# PGTN_daisy1_controls.net
KiCad netlist of a schematic drawn in EAGLE
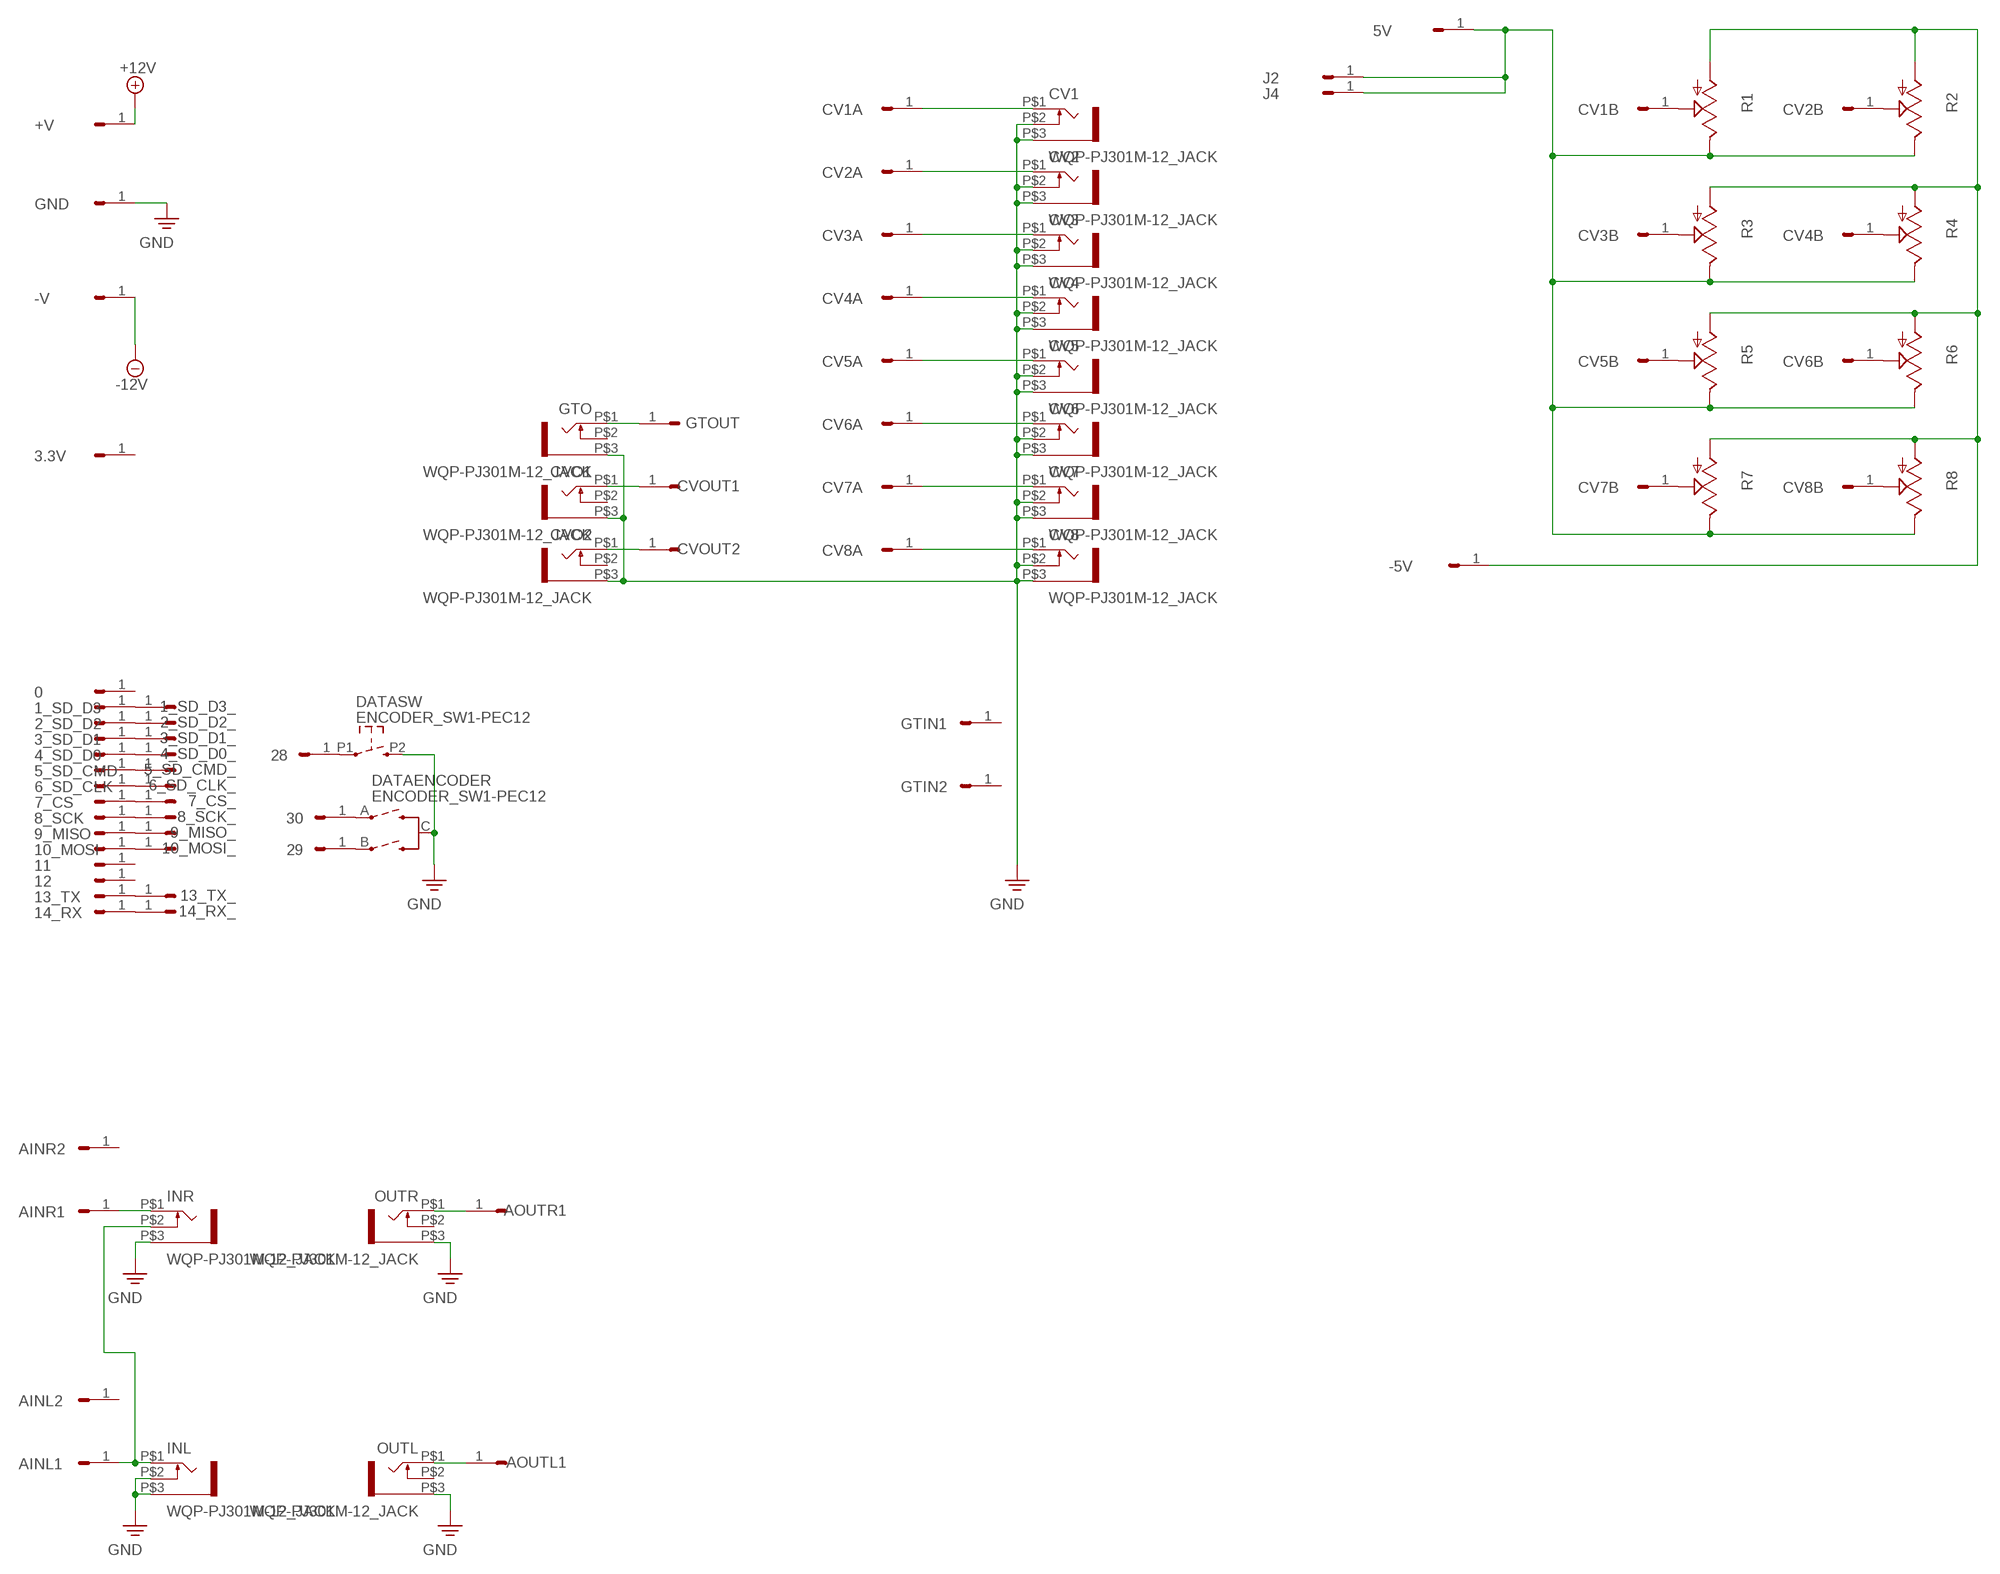
[diagram p0: schematic, sheet 1]

(export (version "E")
  (design (tool "Eeschema 10.0.6"))
  (components
    (comp (ref "+V")
      (value "HEADER/MALE/01")
      (footprint "eagle-import:HEADER_MALE_01")
      (fields (field (name "SPICEPREFIX") "X"))
      (libsource (lib "eagle-import") (part "HEADER/MALE/01"))
    )
    (comp (ref "-5V")
      (value "HEADER/MALE/01")
      (footprint "eagle-import:HEADER_MALE_01")
      (fields (field (name "SPICEPREFIX") "X"))
      (libsource (lib "eagle-import") (part "HEADER/MALE/01"))
    )
    (comp (ref "-V")
      (value "HEADER/MALE/01")
      (footprint "eagle-import:HEADER_MALE_01")
      (fields (field (name "SPICEPREFIX") "X"))
      (libsource (lib "eagle-import") (part "HEADER/MALE/01"))
    )
    (comp (ref "0")
      (value "HEADER/MALE/01")
      (footprint "eagle-import:HEADER_MALE_01")
      (fields (field (name "SPICEPREFIX") "X"))
      (libsource (lib "eagle-import") (part "HEADER/MALE/01"))
    )
    (comp (ref "1_SD_D3")
      (value "HEADER/MALE/01")
      (footprint "eagle-import:HEADER_MALE_01")
      (fields (field (name "SPICEPREFIX") "X"))
      (libsource (lib "eagle-import") (part "HEADER/MALE/01"))
    )
    (comp (ref "1_SD_D3_")
      (value "HEADER/MALE/01")
      (footprint "eagle-import:HEADER_MALE_01")
      (fields (field (name "SPICEPREFIX") "X"))
      (libsource (lib "eagle-import") (part "HEADER/MALE/01"))
    )
    (comp (ref "2_SD_D2")
      (value "HEADER/MALE/01")
      (footprint "eagle-import:HEADER_MALE_01")
      (fields (field (name "SPICEPREFIX") "X"))
      (libsource (lib "eagle-import") (part "HEADER/MALE/01"))
    )
    (comp (ref "2_SD_D2_")
      (value "HEADER/MALE/01")
      (footprint "eagle-import:HEADER_MALE_01")
      (fields (field (name "SPICEPREFIX") "X"))
      (libsource (lib "eagle-import") (part "HEADER/MALE/01"))
    )
    (comp (ref "3.3V")
      (value "HEADER/MALE/01")
      (footprint "eagle-import:HEADER_MALE_01")
      (fields (field (name "SPICEPREFIX") "X"))
      (libsource (lib "eagle-import") (part "HEADER/MALE/01"))
    )
    (comp (ref "3_SD_D1")
      (value "HEADER/MALE/01")
      (footprint "eagle-import:HEADER_MALE_01")
      (fields (field (name "SPICEPREFIX") "X"))
      (libsource (lib "eagle-import") (part "HEADER/MALE/01"))
    )
    (comp (ref "3_SD_D1_")
      (value "HEADER/MALE/01")
      (footprint "eagle-import:HEADER_MALE_01")
      (fields (field (name "SPICEPREFIX") "X"))
      (libsource (lib "eagle-import") (part "HEADER/MALE/01"))
    )
    (comp (ref "4_SD_D0")
      (value "HEADER/MALE/01")
      (footprint "eagle-import:HEADER_MALE_01")
      (fields (field (name "SPICEPREFIX") "X"))
      (libsource (lib "eagle-import") (part "HEADER/MALE/01"))
    )
    (comp (ref "4_SD_D0_")
      (value "HEADER/MALE/01")
      (footprint "eagle-import:HEADER_MALE_01")
      (fields (field (name "SPICEPREFIX") "X"))
      (libsource (lib "eagle-import") (part "HEADER/MALE/01"))
    )
    (comp (ref "5V")
      (value "HEADER/MALE/01")
      (footprint "eagle-import:HEADER_MALE_01")
      (fields (field (name "SPICEPREFIX") "X"))
      (libsource (lib "eagle-import") (part "HEADER/MALE/01"))
    )
    (comp (ref "5_SD_CMD")
      (value "HEADER/MALE/01")
      (footprint "eagle-import:HEADER_MALE_01")
      (fields (field (name "SPICEPREFIX") "X"))
      (libsource (lib "eagle-import") (part "HEADER/MALE/01"))
    )
    (comp (ref "5_SD_CMD_")
      (value "HEADER/MALE/01")
      (footprint "eagle-import:HEADER_MALE_01")
      (fields (field (name "SPICEPREFIX") "X"))
      (libsource (lib "eagle-import") (part "HEADER/MALE/01"))
    )
    (comp (ref "6_SD_CLK")
      (value "HEADER/MALE/01")
      (footprint "eagle-import:HEADER_MALE_01")
      (fields (field (name "SPICEPREFIX") "X"))
      (libsource (lib "eagle-import") (part "HEADER/MALE/01"))
    )
    (comp (ref "6_SD_CLK_")
      (value "HEADER/MALE/01")
      (footprint "eagle-import:HEADER_MALE_01")
      (fields (field (name "SPICEPREFIX") "X"))
      (libsource (lib "eagle-import") (part "HEADER/MALE/01"))
    )
    (comp (ref "7_CS")
      (value "HEADER/MALE/01")
      (footprint "eagle-import:HEADER_MALE_01")
      (fields (field (name "SPICEPREFIX") "X"))
      (libsource (lib "eagle-import") (part "HEADER/MALE/01"))
    )
    (comp (ref "7_CS_")
      (value "HEADER/MALE/01")
      (footprint "eagle-import:HEADER_MALE_01")
      (fields (field (name "SPICEPREFIX") "X"))
      (libsource (lib "eagle-import") (part "HEADER/MALE/01"))
    )
    (comp (ref "8_SCK")
      (value "HEADER/MALE/01")
      (footprint "eagle-import:HEADER_MALE_01")
      (fields (field (name "SPICEPREFIX") "X"))
      (libsource (lib "eagle-import") (part "HEADER/MALE/01"))
    )
    (comp (ref "8_SCK_")
      (value "HEADER/MALE/01")
      (footprint "eagle-import:HEADER_MALE_01")
      (fields (field (name "SPICEPREFIX") "X"))
      (libsource (lib "eagle-import") (part "HEADER/MALE/01"))
    )
    (comp (ref "9_MISO")
      (value "HEADER/MALE/01")
      (footprint "eagle-import:HEADER_MALE_01")
      (fields (field (name "SPICEPREFIX") "X"))
      (libsource (lib "eagle-import") (part "HEADER/MALE/01"))
    )
    (comp (ref "9_MISO_")
      (value "HEADER/MALE/01")
      (footprint "eagle-import:HEADER_MALE_01")
      (fields (field (name "SPICEPREFIX") "X"))
      (libsource (lib "eagle-import") (part "HEADER/MALE/01"))
    )
    (comp (ref "10_MOSI")
      (value "HEADER/MALE/01")
      (footprint "eagle-import:HEADER_MALE_01")
      (fields (field (name "SPICEPREFIX") "X"))
      (libsource (lib "eagle-import") (part "HEADER/MALE/01"))
    )
    (comp (ref "10_MOSI_")
      (value "HEADER/MALE/01")
      (footprint "eagle-import:HEADER_MALE_01")
      (fields (field (name "SPICEPREFIX") "X"))
      (libsource (lib "eagle-import") (part "HEADER/MALE/01"))
    )
    (comp (ref "11")
      (value "HEADER/MALE/01")
      (footprint "eagle-import:HEADER_MALE_01")
      (fields (field (name "SPICEPREFIX") "X"))
      (libsource (lib "eagle-import") (part "HEADER/MALE/01"))
    )
    (comp (ref "12")
      (value "HEADER/MALE/01")
      (footprint "eagle-import:HEADER_MALE_01")
      (fields (field (name "SPICEPREFIX") "X"))
      (libsource (lib "eagle-import") (part "HEADER/MALE/01"))
    )
    (comp (ref "13_TX")
      (value "HEADER/MALE/01")
      (footprint "eagle-import:HEADER_MALE_01")
      (fields (field (name "SPICEPREFIX") "X"))
      (libsource (lib "eagle-import") (part "HEADER/MALE/01"))
    )
    (comp (ref "13_TX_")
      (value "HEADER/MALE/01")
      (footprint "eagle-import:HEADER_MALE_01")
      (fields (field (name "SPICEPREFIX") "X"))
      (libsource (lib "eagle-import") (part "HEADER/MALE/01"))
    )
    (comp (ref "14_RX")
      (value "HEADER/MALE/01")
      (footprint "eagle-import:HEADER_MALE_01")
      (fields (field (name "SPICEPREFIX") "X"))
      (libsource (lib "eagle-import") (part "HEADER/MALE/01"))
    )
    (comp (ref "14_RX_")
      (value "HEADER/MALE/01")
      (footprint "eagle-import:HEADER_MALE_01")
      (fields (field (name "SPICEPREFIX") "X"))
      (libsource (lib "eagle-import") (part "HEADER/MALE/01"))
    )
    (comp (ref "28")
      (value "HEADER/MALE/01")
      (footprint "eagle-import:HEADER_MALE_01")
      (fields (field (name "SPICEPREFIX") "X"))
      (libsource (lib "eagle-import") (part "HEADER/MALE/01"))
    )
    (comp (ref "29")
      (value "HEADER/MALE/01")
      (footprint "eagle-import:HEADER_MALE_01")
      (fields (field (name "SPICEPREFIX") "X"))
      (libsource (lib "eagle-import") (part "HEADER/MALE/01"))
    )
    (comp (ref "30")
      (value "HEADER/MALE/01")
      (footprint "eagle-import:HEADER_MALE_01")
      (fields (field (name "SPICEPREFIX") "X"))
      (libsource (lib "eagle-import") (part "HEADER/MALE/01"))
    )
    (comp (ref "AINL1")
      (value "HEADER/MALE/01")
      (footprint "eagle-import:HEADER_MALE_01")
      (fields (field (name "SPICEPREFIX") "X"))
      (libsource (lib "eagle-import") (part "HEADER/MALE/01"))
    )
    (comp (ref "AINL2")
      (value "HEADER/MALE/01")
      (footprint "eagle-import:HEADER_MALE_01")
      (fields (field (name "SPICEPREFIX") "X"))
      (libsource (lib "eagle-import") (part "HEADER/MALE/01"))
    )
    (comp (ref "AINR1")
      (value "HEADER/MALE/01")
      (footprint "eagle-import:HEADER_MALE_01")
      (fields (field (name "SPICEPREFIX") "X"))
      (libsource (lib "eagle-import") (part "HEADER/MALE/01"))
    )
    (comp (ref "AINR2")
      (value "HEADER/MALE/01")
      (footprint "eagle-import:HEADER_MALE_01")
      (fields (field (name "SPICEPREFIX") "X"))
      (libsource (lib "eagle-import") (part "HEADER/MALE/01"))
    )
    (comp (ref "AOUTL1")
      (value "HEADER/MALE/01")
      (footprint "eagle-import:HEADER_MALE_01")
      (fields (field (name "SPICEPREFIX") "X"))
      (libsource (lib "eagle-import") (part "HEADER/MALE/01"))
    )
    (comp (ref "AOUTR1")
      (value "HEADER/MALE/01")
      (footprint "eagle-import:HEADER_MALE_01")
      (fields (field (name "SPICEPREFIX") "X"))
      (libsource (lib "eagle-import") (part "HEADER/MALE/01"))
    )
    (comp (ref "CV1")
      (value "WQP-PJ301M-12_JACK")
      (footprint "eagle-import:WQP-PJ301M-12_JACK")
      (libsource (lib "eagle-import") (part "WQP-PJ301M-12_JACK"))
    )
    (comp (ref "CV1A")
      (value "HEADER/MALE/01")
      (footprint "eagle-import:HEADER_MALE_01")
      (fields (field (name "SPICEPREFIX") "X"))
      (libsource (lib "eagle-import") (part "HEADER/MALE/01"))
    )
    (comp (ref "CV1B")
      (value "HEADER/MALE/01")
      (footprint "eagle-import:HEADER_MALE_01")
      (fields (field (name "SPICEPREFIX") "X"))
      (libsource (lib "eagle-import") (part "HEADER/MALE/01"))
    )
    (comp (ref "CV2")
      (value "WQP-PJ301M-12_JACK")
      (footprint "eagle-import:WQP-PJ301M-12_JACK")
      (libsource (lib "eagle-import") (part "WQP-PJ301M-12_JACK"))
    )
    (comp (ref "CV2A")
      (value "HEADER/MALE/01")
      (footprint "eagle-import:HEADER_MALE_01")
      (fields (field (name "SPICEPREFIX") "X"))
      (libsource (lib "eagle-import") (part "HEADER/MALE/01"))
    )
    (comp (ref "CV2B")
      (value "HEADER/MALE/01")
      (footprint "eagle-import:HEADER_MALE_01")
      (fields (field (name "SPICEPREFIX") "X"))
      (libsource (lib "eagle-import") (part "HEADER/MALE/01"))
    )
    (comp (ref "CV3")
      (value "WQP-PJ301M-12_JACK")
      (footprint "eagle-import:WQP-PJ301M-12_JACK")
      (libsource (lib "eagle-import") (part "WQP-PJ301M-12_JACK"))
    )
    (comp (ref "CV3A")
      (value "HEADER/MALE/01")
      (footprint "eagle-import:HEADER_MALE_01")
      (fields (field (name "SPICEPREFIX") "X"))
      (libsource (lib "eagle-import") (part "HEADER/MALE/01"))
    )
    (comp (ref "CV3B")
      (value "HEADER/MALE/01")
      (footprint "eagle-import:HEADER_MALE_01")
      (fields (field (name "SPICEPREFIX") "X"))
      (libsource (lib "eagle-import") (part "HEADER/MALE/01"))
    )
    (comp (ref "CV4")
      (value "WQP-PJ301M-12_JACK")
      (footprint "eagle-import:WQP-PJ301M-12_JACK")
      (libsource (lib "eagle-import") (part "WQP-PJ301M-12_JACK"))
    )
    (comp (ref "CV4A")
      (value "HEADER/MALE/01")
      (footprint "eagle-import:HEADER_MALE_01")
      (fields (field (name "SPICEPREFIX") "X"))
      (libsource (lib "eagle-import") (part "HEADER/MALE/01"))
    )
    (comp (ref "CV4B")
      (value "HEADER/MALE/01")
      (footprint "eagle-import:HEADER_MALE_01")
      (fields (field (name "SPICEPREFIX") "X"))
      (libsource (lib "eagle-import") (part "HEADER/MALE/01"))
    )
    (comp (ref "CV5")
      (value "WQP-PJ301M-12_JACK")
      (footprint "eagle-import:WQP-PJ301M-12_JACK")
      (libsource (lib "eagle-import") (part "WQP-PJ301M-12_JACK"))
    )
    (comp (ref "CV5A")
      (value "HEADER/MALE/01")
      (footprint "eagle-import:HEADER_MALE_01")
      (fields (field (name "SPICEPREFIX") "X"))
      (libsource (lib "eagle-import") (part "HEADER/MALE/01"))
    )
    (comp (ref "CV5B")
      (value "HEADER/MALE/01")
      (footprint "eagle-import:HEADER_MALE_01")
      (fields (field (name "SPICEPREFIX") "X"))
      (libsource (lib "eagle-import") (part "HEADER/MALE/01"))
    )
    (comp (ref "CV6")
      (value "WQP-PJ301M-12_JACK")
      (footprint "eagle-import:WQP-PJ301M-12_JACK")
      (libsource (lib "eagle-import") (part "WQP-PJ301M-12_JACK"))
    )
    (comp (ref "CV6A")
      (value "HEADER/MALE/01")
      (footprint "eagle-import:HEADER_MALE_01")
      (fields (field (name "SPICEPREFIX") "X"))
      (libsource (lib "eagle-import") (part "HEADER/MALE/01"))
    )
    (comp (ref "CV6B")
      (value "HEADER/MALE/01")
      (footprint "eagle-import:HEADER_MALE_01")
      (fields (field (name "SPICEPREFIX") "X"))
      (libsource (lib "eagle-import") (part "HEADER/MALE/01"))
    )
    (comp (ref "CV7")
      (value "WQP-PJ301M-12_JACK")
      (footprint "eagle-import:WQP-PJ301M-12_JACK")
      (libsource (lib "eagle-import") (part "WQP-PJ301M-12_JACK"))
    )
    (comp (ref "CV7A")
      (value "HEADER/MALE/01")
      (footprint "eagle-import:HEADER_MALE_01")
      (fields (field (name "SPICEPREFIX") "X"))
      (libsource (lib "eagle-import") (part "HEADER/MALE/01"))
    )
    (comp (ref "CV7B")
      (value "HEADER/MALE/01")
      (footprint "eagle-import:HEADER_MALE_01")
      (fields (field (name "SPICEPREFIX") "X"))
      (libsource (lib "eagle-import") (part "HEADER/MALE/01"))
    )
    (comp (ref "CV8")
      (value "WQP-PJ301M-12_JACK")
      (footprint "eagle-import:WQP-PJ301M-12_JACK")
      (libsource (lib "eagle-import") (part "WQP-PJ301M-12_JACK"))
    )
    (comp (ref "CV8A")
      (value "HEADER/MALE/01")
      (footprint "eagle-import:HEADER_MALE_01")
      (fields (field (name "SPICEPREFIX") "X"))
      (libsource (lib "eagle-import") (part "HEADER/MALE/01"))
    )
    (comp (ref "CV8B")
      (value "HEADER/MALE/01")
      (footprint "eagle-import:HEADER_MALE_01")
      (fields (field (name "SPICEPREFIX") "X"))
      (libsource (lib "eagle-import") (part "HEADER/MALE/01"))
    )
    (comp (ref "CVO1")
      (value "WQP-PJ301M-12_JACK")
      (footprint "eagle-import:WQP-PJ301M-12_JACK")
      (libsource (lib "eagle-import") (part "WQP-PJ301M-12_JACK"))
    )
    (comp (ref "CVO2")
      (value "WQP-PJ301M-12_JACK")
      (footprint "eagle-import:WQP-PJ301M-12_JACK")
      (libsource (lib "eagle-import") (part "WQP-PJ301M-12_JACK"))
    )
    (comp (ref "CVOUT1")
      (value "HEADER/MALE/01")
      (footprint "eagle-import:HEADER_MALE_01")
      (fields (field (name "SPICEPREFIX") "X"))
      (libsource (lib "eagle-import") (part "HEADER/MALE/01"))
    )
    (comp (ref "CVOUT2")
      (value "HEADER/MALE/01")
      (footprint "eagle-import:HEADER_MALE_01")
      (fields (field (name "SPICEPREFIX") "X"))
      (libsource (lib "eagle-import") (part "HEADER/MALE/01"))
    )
    (comp (ref "DATA")
      (value "ENCODER_SW1-PEC12")
      (footprint "eagle-import:PEC12_INCREMENTAL_ENCODER")
      (libsource (lib "eagle-import") (part "ENCODER_SW1-PEC12"))
    )
    (comp (ref "GND")
      (value "HEADER/MALE/01")
      (footprint "eagle-import:HEADER_MALE_01")
      (fields (field (name "SPICEPREFIX") "X"))
      (libsource (lib "eagle-import") (part "HEADER/MALE/01"))
    )
    (comp (ref "GTIN1")
      (value "HEADER/MALE/01")
      (footprint "eagle-import:HEADER_MALE_01")
      (fields (field (name "SPICEPREFIX") "X"))
      (libsource (lib "eagle-import") (part "HEADER/MALE/01"))
    )
    (comp (ref "GTIN2")
      (value "HEADER/MALE/01")
      (footprint "eagle-import:HEADER_MALE_01")
      (fields (field (name "SPICEPREFIX") "X"))
      (libsource (lib "eagle-import") (part "HEADER/MALE/01"))
    )
    (comp (ref "GTO")
      (value "WQP-PJ301M-12_JACK")
      (footprint "eagle-import:WQP-PJ301M-12_JACK")
      (libsource (lib "eagle-import") (part "WQP-PJ301M-12_JACK"))
    )
    (comp (ref "GTOUT")
      (value "HEADER/MALE/01")
      (footprint "eagle-import:HEADER_MALE_01")
      (fields (field (name "SPICEPREFIX") "X"))
      (libsource (lib "eagle-import") (part "HEADER/MALE/01"))
    )
    (comp (ref "INL")
      (value "WQP-PJ301M-12_JACK")
      (footprint "eagle-import:WQP-PJ301M-12_JACK")
      (libsource (lib "eagle-import") (part "WQP-PJ301M-12_JACK"))
    )
    (comp (ref "INR")
      (value "WQP-PJ301M-12_JACK")
      (footprint "eagle-import:WQP-PJ301M-12_JACK")
      (libsource (lib "eagle-import") (part "WQP-PJ301M-12_JACK"))
    )
    (comp (ref "J2")
      (value "HEADER/MALE/01")
      (footprint "eagle-import:HEADER_MALE_01")
      (fields (field (name "SPICEPREFIX") "X"))
      (libsource (lib "eagle-import") (part "HEADER/MALE/01"))
    )
    (comp (ref "J4")
      (value "HEADER/MALE/01")
      (footprint "eagle-import:HEADER_MALE_01")
      (fields (field (name "SPICEPREFIX") "X"))
      (libsource (lib "eagle-import") (part "HEADER/MALE/01"))
    )
    (comp (ref "OUTL")
      (value "WQP-PJ301M-12_JACK")
      (footprint "eagle-import:WQP-PJ301M-12_JACK")
      (libsource (lib "eagle-import") (part "WQP-PJ301M-12_JACK"))
    )
    (comp (ref "OUTR")
      (value "WQP-PJ301M-12_JACK")
      (footprint "eagle-import:WQP-PJ301M-12_JACK")
      (libsource (lib "eagle-import") (part "WQP-PJ301M-12_JACK"))
    )
    (comp (ref "R1")
      (value "9MM_SNAP-IN_POT_")
      (footprint "eagle-import:9MM_SNAP-IN_POT")
      (libsource (lib "eagle-import") (part "9MM_SNAP-IN_POT_"))
    )
    (comp (ref "R2")
      (value "9MM_SNAP-IN_POT_")
      (footprint "eagle-import:9MM_SNAP-IN_POT")
      (libsource (lib "eagle-import") (part "9MM_SNAP-IN_POT_"))
    )
    (comp (ref "R3")
      (value "9MM_SNAP-IN_POT_")
      (footprint "eagle-import:9MM_SNAP-IN_POT")
      (libsource (lib "eagle-import") (part "9MM_SNAP-IN_POT_"))
    )
    (comp (ref "R4")
      (value "9MM_SNAP-IN_POT_")
      (footprint "eagle-import:9MM_SNAP-IN_POT")
      (libsource (lib "eagle-import") (part "9MM_SNAP-IN_POT_"))
    )
    (comp (ref "R5")
      (value "9MM_SNAP-IN_POT_")
      (footprint "eagle-import:9MM_SNAP-IN_POT")
      (libsource (lib "eagle-import") (part "9MM_SNAP-IN_POT_"))
    )
    (comp (ref "R6")
      (value "9MM_SNAP-IN_POT_")
      (footprint "eagle-import:9MM_SNAP-IN_POT")
      (libsource (lib "eagle-import") (part "9MM_SNAP-IN_POT_"))
    )
    (comp (ref "R7")
      (value "9MM_SNAP-IN_POT_")
      (footprint "eagle-import:9MM_SNAP-IN_POT")
      (libsource (lib "eagle-import") (part "9MM_SNAP-IN_POT_"))
    )
    (comp (ref "R8")
      (value "9MM_SNAP-IN_POT_")
      (footprint "eagle-import:9MM_SNAP-IN_POT")
      (libsource (lib "eagle-import") (part "9MM_SNAP-IN_POT_"))
    )
  )
  (nets
    (net (code "1") (name "+12V") (class "Default")
      (node (ref "+V") (pin "1") (pinfunction "3_1") (pintype "passive"))
    )
    (net (code "2") (name "-12V") (class "Default")
      (node (ref "-V") (pin "1") (pinfunction "3_1") (pintype "passive"))
    )
    (net (code "3") (name "GND") (class "Default")
      (node (ref "CV1") (pin "P$2") (pinfunction "3_P$2") (pintype "passive"))
      (node (ref "CV1") (pin "P$3") (pinfunction "1_P$3") (pintype "passive"))
      (node (ref "CV2") (pin "P$2") (pinfunction "3_P$2") (pintype "passive"))
      (node (ref "CV2") (pin "P$3") (pinfunction "1_P$3") (pintype "passive"))
      (node (ref "CV3") (pin "P$2") (pinfunction "3_P$2") (pintype "passive"))
      (node (ref "CV3") (pin "P$3") (pinfunction "1_P$3") (pintype "passive"))
      (node (ref "CV4") (pin "P$2") (pinfunction "3_P$2") (pintype "passive"))
      (node (ref "CV4") (pin "P$3") (pinfunction "1_P$3") (pintype "passive"))
      (node (ref "CV5") (pin "P$2") (pinfunction "3_P$2") (pintype "passive"))
      (node (ref "CV5") (pin "P$3") (pinfunction "1_P$3") (pintype "passive"))
      (node (ref "CV6") (pin "P$2") (pinfunction "3_P$2") (pintype "passive"))
      (node (ref "CV6") (pin "P$3") (pinfunction "1_P$3") (pintype "passive"))
      (node (ref "CV7") (pin "P$2") (pinfunction "3_P$2") (pintype "passive"))
      (node (ref "CV7") (pin "P$3") (pinfunction "1_P$3") (pintype "passive"))
      (node (ref "CV8") (pin "P$2") (pinfunction "3_P$2") (pintype "passive"))
      (node (ref "CV8") (pin "P$3") (pinfunction "1_P$3") (pintype "passive"))
      (node (ref "CVO1") (pin "P$3") (pinfunction "1_P$3") (pintype "passive"))
      (node (ref "CVO2") (pin "P$3") (pinfunction "1_P$3") (pintype "passive"))
      (node (ref "DATA") (pin "C") (pinfunction "C_C") (pintype "passive"))
      (node (ref "DATA") (pin "P2") (pinfunction "2_P2") (pintype "passive"))
      (node (ref "GND") (pin "1") (pinfunction "3_1") (pintype "passive"))
      (node (ref "GTO") (pin "P$3") (pinfunction "1_P$3") (pintype "passive"))
      (node (ref "INL") (pin "P$2") (pinfunction "3_P$2") (pintype "passive"))
      (node (ref "INL") (pin "P$3") (pinfunction "1_P$3") (pintype "passive"))
      (node (ref "INR") (pin "P$3") (pinfunction "1_P$3") (pintype "passive"))
      (node (ref "OUTL") (pin "P$3") (pinfunction "1_P$3") (pintype "passive"))
      (node (ref "OUTR") (pin "P$3") (pinfunction "1_P$3") (pintype "passive"))
    )
    (net (code "4") (name "Net-(-5V-3)") (class "Default")
      (node (ref "-5V") (pin "1") (pinfunction "3_1") (pintype "passive"))
      (node (ref "R1") (pin "1") (pinfunction "A_1") (pintype "passive"))
      (node (ref "R2") (pin "1") (pinfunction "A_1") (pintype "passive"))
      (node (ref "R3") (pin "1") (pinfunction "A_1") (pintype "passive"))
      (node (ref "R4") (pin "1") (pinfunction "A_1") (pintype "passive"))
      (node (ref "R5") (pin "1") (pinfunction "A_1") (pintype "passive"))
      (node (ref "R6") (pin "1") (pinfunction "A_1") (pintype "passive"))
      (node (ref "R7") (pin "1") (pinfunction "A_1") (pintype "passive"))
      (node (ref "R8") (pin "1") (pinfunction "A_1") (pintype "passive"))
    )
    (net (code "5") (name "Net-(1_SD_D3-3)") (class "Default")
      (node (ref "1_SD_D3") (pin "1") (pinfunction "3_1") (pintype "passive"))
      (node (ref "1_SD_D3_") (pin "1") (pinfunction "3_1") (pintype "passive"))
    )
    (net (code "6") (name "Net-(2_SD_D2-3)") (class "Default")
      (node (ref "2_SD_D2") (pin "1") (pinfunction "3_1") (pintype "passive"))
      (node (ref "2_SD_D2_") (pin "1") (pinfunction "3_1") (pintype "passive"))
    )
    (net (code "7") (name "Net-(3_SD_D1-3)") (class "Default")
      (node (ref "3_SD_D1") (pin "1") (pinfunction "3_1") (pintype "passive"))
      (node (ref "3_SD_D1_") (pin "1") (pinfunction "3_1") (pintype "passive"))
    )
    (net (code "8") (name "Net-(4_SD_D0-3)") (class "Default")
      (node (ref "4_SD_D0") (pin "1") (pinfunction "3_1") (pintype "passive"))
      (node (ref "4_SD_D0_") (pin "1") (pinfunction "3_1") (pintype "passive"))
    )
    (net (code "9") (name "Net-(5V-3)") (class "Default")
      (node (ref "5V") (pin "1") (pinfunction "3_1") (pintype "passive"))
      (node (ref "J2") (pin "1") (pinfunction "3_1") (pintype "passive"))
      (node (ref "J4") (pin "1") (pinfunction "3_1") (pintype "passive"))
      (node (ref "R1") (pin "3") (pinfunction "E_3") (pintype "passive"))
      (node (ref "R2") (pin "3") (pinfunction "E_3") (pintype "passive"))
      (node (ref "R3") (pin "3") (pinfunction "E_3") (pintype "passive"))
      (node (ref "R4") (pin "3") (pinfunction "E_3") (pintype "passive"))
      (node (ref "R5") (pin "3") (pinfunction "E_3") (pintype "passive"))
      (node (ref "R6") (pin "3") (pinfunction "E_3") (pintype "passive"))
      (node (ref "R7") (pin "3") (pinfunction "E_3") (pintype "passive"))
      (node (ref "R8") (pin "3") (pinfunction "E_3") (pintype "passive"))
    )
    (net (code "10") (name "Net-(5_SD_CMD-3)") (class "Default")
      (node (ref "5_SD_CMD") (pin "1") (pinfunction "3_1") (pintype "passive"))
      (node (ref "5_SD_CMD_") (pin "1") (pinfunction "3_1") (pintype "passive"))
    )
    (net (code "11") (name "Net-(6_SD_CLK-3)") (class "Default")
      (node (ref "6_SD_CLK") (pin "1") (pinfunction "3_1") (pintype "passive"))
      (node (ref "6_SD_CLK_") (pin "1") (pinfunction "3_1") (pintype "passive"))
    )
    (net (code "12") (name "Net-(7_CS-3)") (class "Default")
      (node (ref "7_CS") (pin "1") (pinfunction "3_1") (pintype "passive"))
      (node (ref "7_CS_") (pin "1") (pinfunction "3_1") (pintype "passive"))
    )
    (net (code "13") (name "Net-(8_SCK-3)") (class "Default")
      (node (ref "8_SCK") (pin "1") (pinfunction "3_1") (pintype "passive"))
      (node (ref "8_SCK_") (pin "1") (pinfunction "3_1") (pintype "passive"))
    )
    (net (code "14") (name "Net-(9_MISO-3)") (class "Default")
      (node (ref "9_MISO") (pin "1") (pinfunction "3_1") (pintype "passive"))
      (node (ref "9_MISO_") (pin "1") (pinfunction "3_1") (pintype "passive"))
    )
    (net (code "15") (name "Net-(10_MOSI-3)") (class "Default")
      (node (ref "10_MOSI") (pin "1") (pinfunction "3_1") (pintype "passive"))
      (node (ref "10_MOSI_") (pin "1") (pinfunction "3_1") (pintype "passive"))
    )
    (net (code "16") (name "Net-(13_TX-3)") (class "Default")
      (node (ref "13_TX") (pin "1") (pinfunction "3_1") (pintype "passive"))
      (node (ref "13_TX_") (pin "1") (pinfunction "3_1") (pintype "passive"))
    )
    (net (code "17") (name "Net-(14_RX-3)") (class "Default")
      (node (ref "14_RX") (pin "1") (pinfunction "3_1") (pintype "passive"))
      (node (ref "14_RX_") (pin "1") (pinfunction "3_1") (pintype "passive"))
    )
    (net (code "18") (name "Net-(28-3)") (class "Default")
      (node (ref "28") (pin "1") (pinfunction "3_1") (pintype "passive"))
      (node (ref "DATA") (pin "P1") (pinfunction "1_P1") (pintype "passive"))
    )
    (net (code "19") (name "Net-(29-3)") (class "Default")
      (node (ref "29") (pin "1") (pinfunction "3_1") (pintype "passive"))
      (node (ref "DATA") (pin "B") (pinfunction "B_B") (pintype "passive"))
    )
    (net (code "20") (name "Net-(30-3)") (class "Default")
      (node (ref "30") (pin "1") (pinfunction "3_1") (pintype "passive"))
      (node (ref "DATA") (pin "A") (pinfunction "A_A") (pintype "passive"))
    )
    (net (code "21") (name "Net-(AINL1-3)") (class "Default")
      (node (ref "AINL1") (pin "1") (pinfunction "3_1") (pintype "passive"))
      (node (ref "INL") (pin "P$1") (pinfunction "2_P$1") (pintype "passive"))
      (node (ref "INR") (pin "P$2") (pinfunction "3_P$2") (pintype "passive"))
    )
    (net (code "22") (name "Net-(AINR1-3)") (class "Default")
      (node (ref "AINR1") (pin "1") (pinfunction "3_1") (pintype "passive"))
      (node (ref "INR") (pin "P$1") (pinfunction "2_P$1") (pintype "passive"))
    )
    (net (code "23") (name "Net-(AOUTL1-3)") (class "Default")
      (node (ref "AOUTL1") (pin "1") (pinfunction "3_1") (pintype "passive"))
      (node (ref "OUTL") (pin "P$1") (pinfunction "2_P$1") (pintype "passive"))
    )
    (net (code "24") (name "Net-(AOUTR1-3)") (class "Default")
      (node (ref "AOUTR1") (pin "1") (pinfunction "3_1") (pintype "passive"))
      (node (ref "OUTR") (pin "P$1") (pinfunction "2_P$1") (pintype "passive"))
    )
    (net (code "25") (name "Net-(CV1-2)") (class "Default")
      (node (ref "CV1") (pin "P$1") (pinfunction "2_P$1") (pintype "passive"))
      (node (ref "CV1A") (pin "1") (pinfunction "3_1") (pintype "passive"))
    )
    (net (code "26") (name "Net-(CV1B-3)") (class "Default")
      (node (ref "CV1B") (pin "1") (pinfunction "3_1") (pintype "passive"))
      (node (ref "R1") (pin "2") (pinfunction "S_2") (pintype "passive"))
    )
    (net (code "27") (name "Net-(CV2-2)") (class "Default")
      (node (ref "CV2") (pin "P$1") (pinfunction "2_P$1") (pintype "passive"))
      (node (ref "CV2A") (pin "1") (pinfunction "3_1") (pintype "passive"))
    )
    (net (code "28") (name "Net-(CV2B-3)") (class "Default")
      (node (ref "CV2B") (pin "1") (pinfunction "3_1") (pintype "passive"))
      (node (ref "R2") (pin "2") (pinfunction "S_2") (pintype "passive"))
    )
    (net (code "29") (name "Net-(CV3-2)") (class "Default")
      (node (ref "CV3") (pin "P$1") (pinfunction "2_P$1") (pintype "passive"))
      (node (ref "CV3A") (pin "1") (pinfunction "3_1") (pintype "passive"))
    )
    (net (code "30") (name "Net-(CV3B-3)") (class "Default")
      (node (ref "CV3B") (pin "1") (pinfunction "3_1") (pintype "passive"))
      (node (ref "R3") (pin "2") (pinfunction "S_2") (pintype "passive"))
    )
    (net (code "31") (name "Net-(CV4-2)") (class "Default")
      (node (ref "CV4") (pin "P$1") (pinfunction "2_P$1") (pintype "passive"))
      (node (ref "CV4A") (pin "1") (pinfunction "3_1") (pintype "passive"))
    )
    (net (code "32") (name "Net-(CV4B-3)") (class "Default")
      (node (ref "CV4B") (pin "1") (pinfunction "3_1") (pintype "passive"))
      (node (ref "R4") (pin "2") (pinfunction "S_2") (pintype "passive"))
    )
    (net (code "33") (name "Net-(CV5-2)") (class "Default")
      (node (ref "CV5") (pin "P$1") (pinfunction "2_P$1") (pintype "passive"))
      (node (ref "CV5A") (pin "1") (pinfunction "3_1") (pintype "passive"))
    )
    (net (code "34") (name "Net-(CV5B-3)") (class "Default")
      (node (ref "CV5B") (pin "1") (pinfunction "3_1") (pintype "passive"))
      (node (ref "R5") (pin "2") (pinfunction "S_2") (pintype "passive"))
    )
    (net (code "35") (name "Net-(CV6-2)") (class "Default")
      (node (ref "CV6") (pin "P$1") (pinfunction "2_P$1") (pintype "passive"))
      (node (ref "CV6A") (pin "1") (pinfunction "3_1") (pintype "passive"))
    )
    (net (code "36") (name "Net-(CV6B-3)") (class "Default")
      (node (ref "CV6B") (pin "1") (pinfunction "3_1") (pintype "passive"))
      (node (ref "R6") (pin "2") (pinfunction "S_2") (pintype "passive"))
    )
    (net (code "37") (name "Net-(CV7-2)") (class "Default")
      (node (ref "CV7") (pin "P$1") (pinfunction "2_P$1") (pintype "passive"))
      (node (ref "CV7A") (pin "1") (pinfunction "3_1") (pintype "passive"))
    )
    (net (code "38") (name "Net-(CV7B-3)") (class "Default")
      (node (ref "CV7B") (pin "1") (pinfunction "3_1") (pintype "passive"))
      (node (ref "R7") (pin "2") (pinfunction "S_2") (pintype "passive"))
    )
    (net (code "39") (name "Net-(CV8-2)") (class "Default")
      (node (ref "CV8") (pin "P$1") (pinfunction "2_P$1") (pintype "passive"))
      (node (ref "CV8A") (pin "1") (pinfunction "3_1") (pintype "passive"))
    )
    (net (code "40") (name "Net-(CV8B-3)") (class "Default")
      (node (ref "CV8B") (pin "1") (pinfunction "3_1") (pintype "passive"))
      (node (ref "R8") (pin "2") (pinfunction "S_2") (pintype "passive"))
    )
    (net (code "41") (name "Net-(CVO1-2)") (class "Default")
      (node (ref "CVO1") (pin "P$1") (pinfunction "2_P$1") (pintype "passive"))
      (node (ref "CVOUT1") (pin "1") (pinfunction "3_1") (pintype "passive"))
    )
    (net (code "42") (name "Net-(CVO2-2)") (class "Default")
      (node (ref "CVO2") (pin "P$1") (pinfunction "2_P$1") (pintype "passive"))
      (node (ref "CVOUT2") (pin "1") (pinfunction "3_1") (pintype "passive"))
    )
    (net (code "43") (name "Net-(GTO-2)") (class "Default")
      (node (ref "GTO") (pin "P$1") (pinfunction "2_P$1") (pintype "passive"))
      (node (ref "GTOUT") (pin "1") (pinfunction "3_1") (pintype "passive"))
    )
    (net (code "44") (name "unconnected-(0-3-Pad1)") (class "Default")
      (node (ref "0") (pin "1") (pinfunction "3_1") (pintype "passive"))
    )
    (net (code "45") (name "unconnected-(3.3V-3-Pad1)") (class "Default")
      (node (ref "3.3V") (pin "1") (pinfunction "3_1") (pintype "passive"))
    )
    (net (code "46") (name "unconnected-(11-3-Pad1)") (class "Default")
      (node (ref "11") (pin "1") (pinfunction "3_1") (pintype "passive"))
    )
    (net (code "47") (name "unconnected-(12-3-Pad1)") (class "Default")
      (node (ref "12") (pin "1") (pinfunction "3_1") (pintype "passive"))
    )
    (net (code "48") (name "unconnected-(AINL2-3-Pad1)") (class "Default")
      (node (ref "AINL2") (pin "1") (pinfunction "3_1") (pintype "passive"))
    )
    (net (code "49") (name "unconnected-(AINR2-3-Pad1)") (class "Default")
      (node (ref "AINR2") (pin "1") (pinfunction "3_1") (pintype "passive"))
    )
    (net (code "50") (name "unconnected-(CVO1-3-PadP$2)") (class "Default")
      (node (ref "CVO1") (pin "P$2") (pinfunction "3_P$2") (pintype "passive"))
    )
    (net (code "51") (name "unconnected-(CVO2-3-PadP$2)") (class "Default")
      (node (ref "CVO2") (pin "P$2") (pinfunction "3_P$2") (pintype "passive"))
    )
    (net (code "52") (name "unconnected-(GTIN1-3-Pad1)") (class "Default")
      (node (ref "GTIN1") (pin "1") (pinfunction "3_1") (pintype "passive"))
    )
    (net (code "53") (name "unconnected-(GTIN2-3-Pad1)") (class "Default")
      (node (ref "GTIN2") (pin "1") (pinfunction "3_1") (pintype "passive"))
    )
    (net (code "54") (name "unconnected-(GTO-3-PadP$2)") (class "Default")
      (node (ref "GTO") (pin "P$2") (pinfunction "3_P$2") (pintype "passive"))
    )
    (net (code "55") (name "unconnected-(OUTL-3-PadP$2)") (class "Default")
      (node (ref "OUTL") (pin "P$2") (pinfunction "3_P$2") (pintype "passive"))
    )
    (net (code "56") (name "unconnected-(OUTR-3-PadP$2)") (class "Default")
      (node (ref "OUTR") (pin "P$2") (pinfunction "3_P$2") (pintype "passive"))
    )
  )
)
